# l-drv_h2.net
KiCad netlist of a schematic drawn in EAGLE
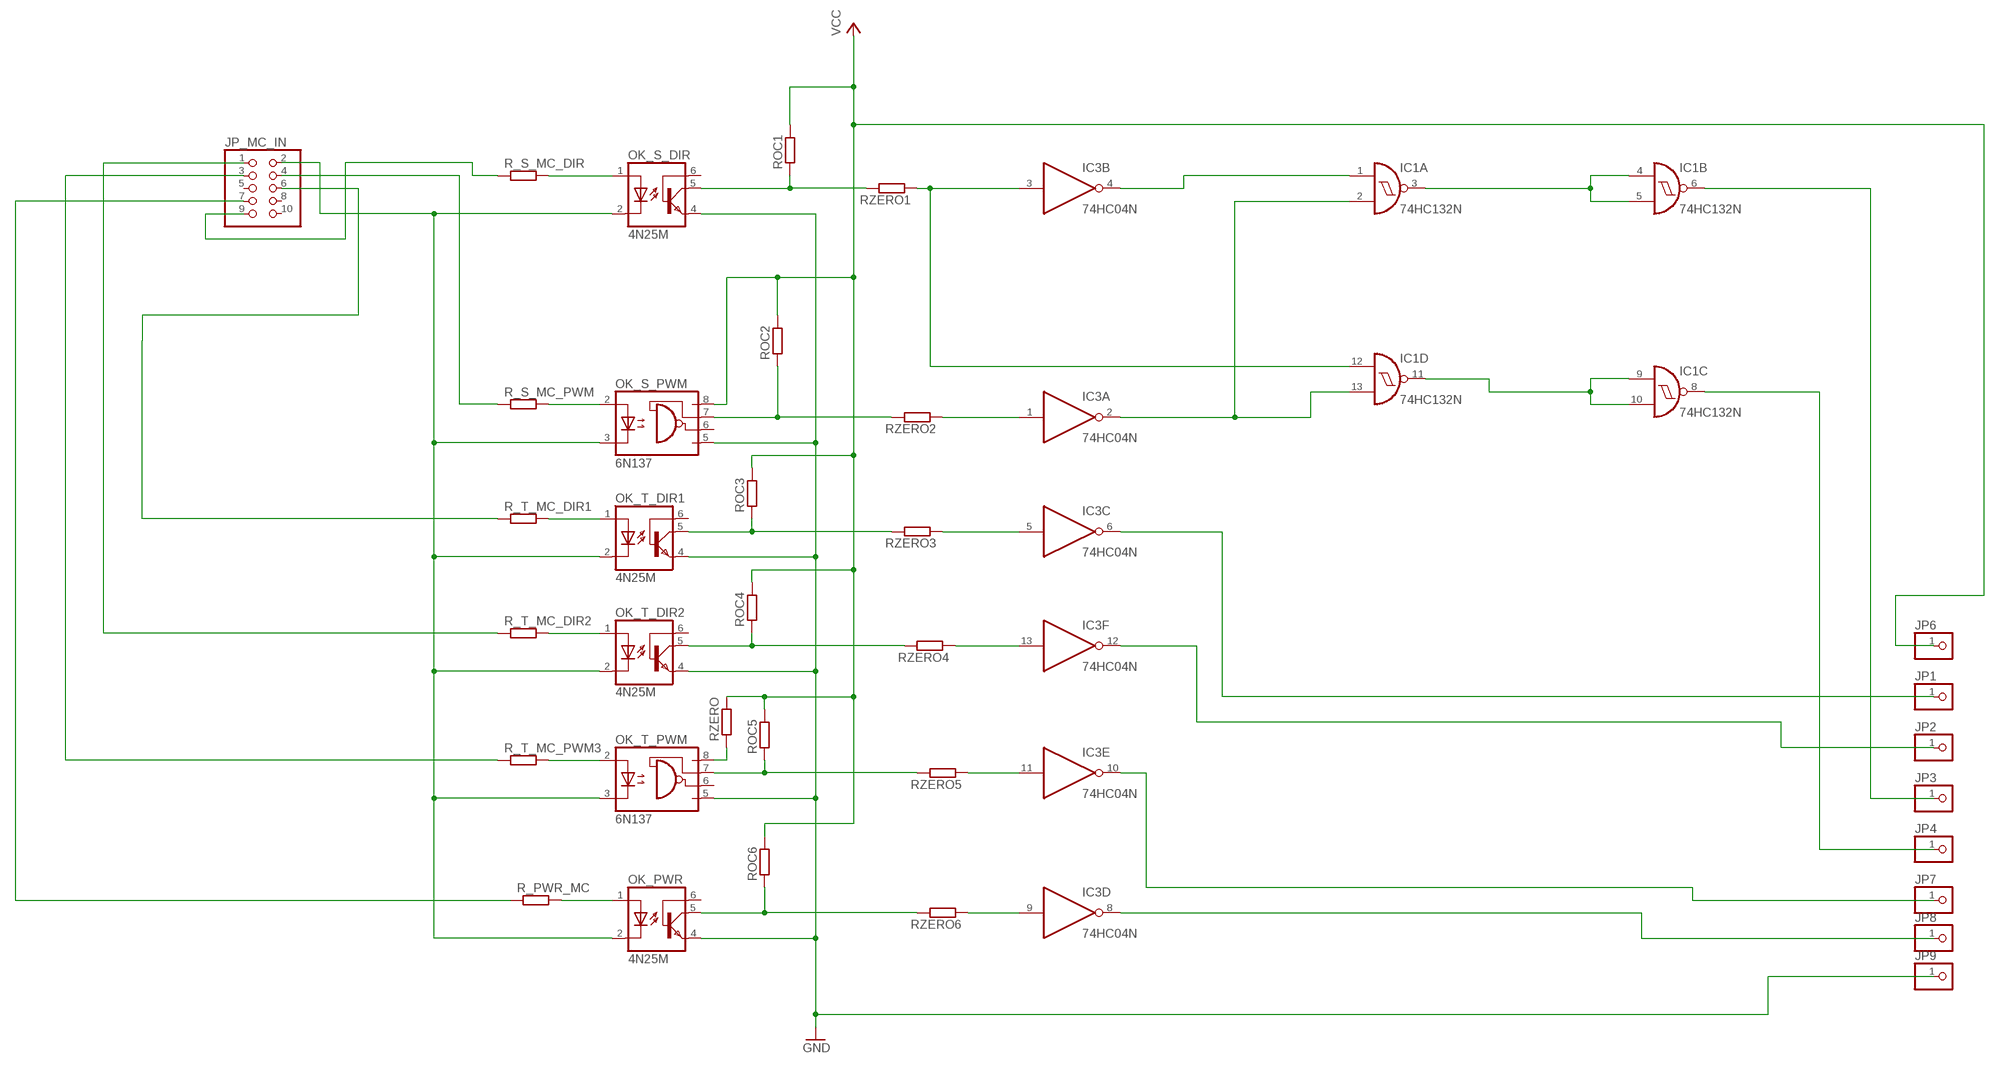
[diagram p0: schematic, sheet 1]

(export (version "E")
  (design (tool "Eeschema 10.0.6"))
  (components
    (comp (ref "IC1")
      (value "74HC132N")
      (footprint "eagle-import:DIL14")
      (libsource (lib "eagle-import") (part "74132NHC"))
    )
    (comp (ref "IC3")
      (value "74HC04N")
      (footprint "eagle-import:DIL14")
      (libsource (lib "eagle-import") (part "7404NHC"))
    )
    (comp (ref "JP1")
      (value "PINHD-1X1")
      (footprint "eagle-import:1X01")
      (libsource (lib "eagle-import") (part "PINHD-1X1"))
    )
    (comp (ref "JP2")
      (value "PINHD-1X1")
      (footprint "eagle-import:1X01")
      (libsource (lib "eagle-import") (part "PINHD-1X1"))
    )
    (comp (ref "JP3")
      (value "PINHD-1X1")
      (footprint "eagle-import:1X01")
      (libsource (lib "eagle-import") (part "PINHD-1X1"))
    )
    (comp (ref "JP4")
      (value "PINHD-1X1")
      (footprint "eagle-import:1X01")
      (libsource (lib "eagle-import") (part "PINHD-1X1"))
    )
    (comp (ref "JP6")
      (value "PINHD-1X1")
      (footprint "eagle-import:1X01")
      (libsource (lib "eagle-import") (part "PINHD-1X1"))
    )
    (comp (ref "JP7")
      (value "PINHD-1X1")
      (footprint "eagle-import:1X01")
      (libsource (lib "eagle-import") (part "PINHD-1X1"))
    )
    (comp (ref "JP8")
      (value "PINHD-1X1")
      (footprint "eagle-import:1X01")
      (libsource (lib "eagle-import") (part "PINHD-1X1"))
    )
    (comp (ref "JP9")
      (value "PINHD-1X1")
      (footprint "eagle-import:1X01")
      (libsource (lib "eagle-import") (part "PINHD-1X1"))
    )
    (comp (ref "JP_MC_IN")
      (value "PINHD-2X5")
      (footprint "eagle-import:2X05")
      (libsource (lib "eagle-import") (part "PINHD-2X5"))
    )
    (comp (ref "OK_PWR")
      (value "4N25M")
      (footprint "eagle-import:DIL06")
      (fields (field (name "MPN") "4N25-M"))
      (libsource (lib "eagle-import") (part "4N?M25"))
    )
    (comp (ref "OK_S_DIR")
      (value "4N25M")
      (footprint "eagle-import:DIL06")
      (fields (field (name "MPN") "4N25-M"))
      (libsource (lib "eagle-import") (part "4N?M25"))
    )
    (comp (ref "OK_S_PWM")
      (value "6N137")
      (footprint "eagle-import:DIL08")
      (libsource (lib "eagle-import") (part "6N137"))
    )
    (comp (ref "OK_T_DIR1")
      (value "4N25M")
      (footprint "eagle-import:DIL06")
      (fields (field (name "MPN") "4N25-M"))
      (libsource (lib "eagle-import") (part "4N?M25"))
    )
    (comp (ref "OK_T_DIR2")
      (value "4N25M")
      (footprint "eagle-import:DIL06")
      (fields (field (name "MPN") "4N25-M"))
      (libsource (lib "eagle-import") (part "4N?M25"))
    )
    (comp (ref "OK_T_PWM")
      (value "6N137")
      (footprint "eagle-import:DIL08")
      (libsource (lib "eagle-import") (part "6N137"))
    )
    (comp (ref "ROC1")
      (value "R-EU_0204/5")
      (footprint "eagle-import:0204_5")
      (libsource (lib "eagle-import") (part "R-EU_0204/5"))
    )
    (comp (ref "ROC2")
      (value "R-EU_0204/5")
      (footprint "eagle-import:0204_5")
      (libsource (lib "eagle-import") (part "R-EU_0204/5"))
    )
    (comp (ref "ROC3")
      (value "R-EU_0204/5")
      (footprint "eagle-import:0204_5")
      (libsource (lib "eagle-import") (part "R-EU_0204/5"))
    )
    (comp (ref "ROC4")
      (value "R-EU_0204/5")
      (footprint "eagle-import:0204_5")
      (libsource (lib "eagle-import") (part "R-EU_0204/5"))
    )
    (comp (ref "ROC5")
      (value "R-EU_0204/5")
      (footprint "eagle-import:0204_5")
      (libsource (lib "eagle-import") (part "R-EU_0204/5"))
    )
    (comp (ref "ROC6")
      (value "R-EU_0204/5")
      (footprint "eagle-import:0204_5")
      (libsource (lib "eagle-import") (part "R-EU_0204/5"))
    )
    (comp (ref "RZERO")
      (value "R-EU_0204/5")
      (footprint "eagle-import:0204_5")
      (libsource (lib "eagle-import") (part "R-EU_0204/5"))
    )
    (comp (ref "RZERO1")
      (value "R-EU_0204/5")
      (footprint "eagle-import:0204_5")
      (libsource (lib "eagle-import") (part "R-EU_0204/5"))
    )
    (comp (ref "RZERO2")
      (value "R-EU_0204/5")
      (footprint "eagle-import:0204_5")
      (libsource (lib "eagle-import") (part "R-EU_0204/5"))
    )
    (comp (ref "RZERO3")
      (value "R-EU_0204/5")
      (footprint "eagle-import:0204_5")
      (libsource (lib "eagle-import") (part "R-EU_0204/5"))
    )
    (comp (ref "RZERO4")
      (value "R-EU_0204/5")
      (footprint "eagle-import:0204_5")
      (libsource (lib "eagle-import") (part "R-EU_0204/5"))
    )
    (comp (ref "RZERO5")
      (value "R-EU_0204/5")
      (footprint "eagle-import:0204_5")
      (libsource (lib "eagle-import") (part "R-EU_0204/5"))
    )
    (comp (ref "RZERO6")
      (value "R-EU_0204/5")
      (footprint "eagle-import:0204_5")
      (libsource (lib "eagle-import") (part "R-EU_0204/5"))
    )
    (comp (ref "R_PWR_MC")
      (value "R-EU_0204/5")
      (footprint "eagle-import:0204_5")
      (libsource (lib "eagle-import") (part "R-EU_0204/5"))
    )
    (comp (ref "R_S_MC_DIR")
      (value "R-EU_0204/5")
      (footprint "eagle-import:0204_5")
      (libsource (lib "eagle-import") (part "R-EU_0204/5"))
    )
    (comp (ref "R_S_MC_PWM")
      (value "R-EU_0204/5")
      (footprint "eagle-import:0204_5")
      (libsource (lib "eagle-import") (part "R-EU_0204/5"))
    )
    (comp (ref "R_T_MC_DIR1")
      (value "R-EU_0204/5")
      (footprint "eagle-import:0204_5")
      (libsource (lib "eagle-import") (part "R-EU_0204/5"))
    )
    (comp (ref "R_T_MC_DIR2")
      (value "R-EU_0204/5")
      (footprint "eagle-import:0204_5")
      (libsource (lib "eagle-import") (part "R-EU_0204/5"))
    )
    (comp (ref "R_T_MC_PWM3")
      (value "R-EU_0204/5")
      (footprint "eagle-import:0204_5")
      (libsource (lib "eagle-import") (part "R-EU_0204/5"))
    )
  )
  (nets
    (net (code "1") (name "GND") (class "Default")
      (node (ref "JP9") (pin "1") (pinfunction "1_1") (pintype "passive"))
      (node (ref "OK_PWR") (pin "4") (pinfunction "EMI_4") (pintype "passive"))
      (node (ref "OK_S_DIR") (pin "4") (pinfunction "EMI_4") (pintype "passive"))
      (node (ref "OK_S_PWM") (pin "5") (pinfunction "GND_5") (pintype "passive"))
      (node (ref "OK_T_DIR1") (pin "4") (pinfunction "EMI_4") (pintype "passive"))
      (node (ref "OK_T_DIR2") (pin "4") (pinfunction "EMI_4") (pintype "passive"))
      (node (ref "OK_T_PWM") (pin "5") (pinfunction "GND_5") (pintype "passive"))
    )
    (net (code "2") (name "Net-(IC1A-I0)") (class "Default")
      (node (ref "IC1") (pin "1") (pinfunction "I0_1") (pintype "input"))
      (node (ref "IC3") (pin "4") (pinfunction "O_4") (pintype "output"))
    )
    (net (code "3") (name "Net-(IC1A-I1)") (class "Default")
      (node (ref "IC1") (pin "13") (pinfunction "I1_13") (pintype "input"))
      (node (ref "IC1") (pin "2") (pinfunction "I1_2") (pintype "input"))
      (node (ref "IC3") (pin "2") (pinfunction "O_2") (pintype "output"))
    )
    (net (code "4") (name "Net-(IC1A-O)") (class "Default")
      (node (ref "IC1") (pin "3") (pinfunction "O_3") (pintype "output"))
      (node (ref "IC1") (pin "4") (pinfunction "I0_4") (pintype "input"))
      (node (ref "IC1") (pin "5") (pinfunction "I1_5") (pintype "input"))
    )
    (net (code "5") (name "Net-(IC1B-O)") (class "Default")
      (node (ref "IC1") (pin "6") (pinfunction "O_6") (pintype "output"))
      (node (ref "JP3") (pin "1") (pinfunction "1_1") (pintype "passive"))
    )
    (net (code "6") (name "Net-(IC1C-I0)") (class "Default")
      (node (ref "IC1") (pin "10") (pinfunction "I1_10") (pintype "input"))
      (node (ref "IC1") (pin "11") (pinfunction "O_11") (pintype "output"))
      (node (ref "IC1") (pin "9") (pinfunction "I0_9") (pintype "input"))
    )
    (net (code "7") (name "Net-(IC1C-O)") (class "Default")
      (node (ref "IC1") (pin "8") (pinfunction "O_8") (pintype "output"))
      (node (ref "JP4") (pin "1") (pinfunction "1_1") (pintype "passive"))
    )
    (net (code "8") (name "Net-(IC1D-I0)") (class "Default")
      (node (ref "IC1") (pin "12") (pinfunction "I0_12") (pintype "input"))
      (node (ref "IC3") (pin "3") (pinfunction "I_3") (pintype "input"))
      (node (ref "RZERO1") (pin "1") (pinfunction "1_1") (pintype "passive"))
    )
    (net (code "9") (name "Net-(IC3A-I)") (class "Default")
      (node (ref "IC3") (pin "1") (pinfunction "I_1") (pintype "input"))
      (node (ref "RZERO2") (pin "1") (pinfunction "1_1") (pintype "passive"))
    )
    (net (code "10") (name "Net-(IC3C-I)") (class "Default")
      (node (ref "IC3") (pin "5") (pinfunction "I_5") (pintype "input"))
      (node (ref "RZERO3") (pin "1") (pinfunction "1_1") (pintype "passive"))
    )
    (net (code "11") (name "Net-(IC3C-O)") (class "Default")
      (node (ref "IC3") (pin "6") (pinfunction "O_6") (pintype "output"))
      (node (ref "JP1") (pin "1") (pinfunction "1_1") (pintype "passive"))
    )
    (net (code "12") (name "Net-(IC3D-I)") (class "Default")
      (node (ref "IC3") (pin "9") (pinfunction "I_9") (pintype "input"))
      (node (ref "RZERO6") (pin "1") (pinfunction "1_1") (pintype "passive"))
    )
    (net (code "13") (name "Net-(IC3D-O)") (class "Default")
      (node (ref "IC3") (pin "8") (pinfunction "O_8") (pintype "output"))
      (node (ref "JP8") (pin "1") (pinfunction "1_1") (pintype "passive"))
    )
    (net (code "14") (name "Net-(IC3E-I)") (class "Default")
      (node (ref "IC3") (pin "11") (pinfunction "I_11") (pintype "input"))
      (node (ref "RZERO5") (pin "1") (pinfunction "1_1") (pintype "passive"))
    )
    (net (code "15") (name "Net-(IC3E-O)") (class "Default")
      (node (ref "IC3") (pin "10") (pinfunction "O_10") (pintype "output"))
      (node (ref "JP7") (pin "1") (pinfunction "1_1") (pintype "passive"))
    )
    (net (code "16") (name "Net-(IC3F-I)") (class "Default")
      (node (ref "IC3") (pin "13") (pinfunction "I_13") (pintype "input"))
      (node (ref "RZERO4") (pin "1") (pinfunction "1_1") (pintype "passive"))
    )
    (net (code "17") (name "Net-(IC3F-O)") (class "Default")
      (node (ref "IC3") (pin "12") (pinfunction "O_12") (pintype "output"))
      (node (ref "JP2") (pin "1") (pinfunction "1_1") (pintype "passive"))
    )
    (net (code "18") (name "Net-(JP_MC_IN-Pad1)") (class "Default")
      (node (ref "JP_MC_IN") (pin "1") (pinfunction "1_1") (pintype "passive"))
      (node (ref "R_T_MC_DIR2") (pin "1") (pinfunction "1_1") (pintype "passive"))
    )
    (net (code "19") (name "Net-(JP_MC_IN-Pad3)") (class "Default")
      (node (ref "JP_MC_IN") (pin "3") (pinfunction "3_3") (pintype "passive"))
      (node (ref "R_T_MC_PWM3") (pin "1") (pinfunction "1_1") (pintype "passive"))
    )
    (net (code "20") (name "Net-(JP_MC_IN-Pad4)") (class "Default")
      (node (ref "JP_MC_IN") (pin "4") (pinfunction "4_4") (pintype "passive"))
      (node (ref "R_S_MC_PWM") (pin "1") (pinfunction "1_1") (pintype "passive"))
    )
    (net (code "21") (name "Net-(JP_MC_IN-Pad6)") (class "Default")
      (node (ref "JP_MC_IN") (pin "6") (pinfunction "6_6") (pintype "passive"))
      (node (ref "R_T_MC_DIR1") (pin "1") (pinfunction "1_1") (pintype "passive"))
    )
    (net (code "22") (name "Net-(JP_MC_IN-Pad7)") (class "Default")
      (node (ref "JP_MC_IN") (pin "7") (pinfunction "7_7") (pintype "passive"))
      (node (ref "R_PWR_MC") (pin "1") (pinfunction "1_1") (pintype "passive"))
    )
    (net (code "23") (name "Net-(JP_MC_IN-Pad9)") (class "Default")
      (node (ref "JP_MC_IN") (pin "9") (pinfunction "9_9") (pintype "passive"))
      (node (ref "R_S_MC_DIR") (pin "1") (pinfunction "1_1") (pintype "passive"))
    )
    (net (code "24") (name "Net-(OK_PWR-A)") (class "Default")
      (node (ref "OK_PWR") (pin "1") (pinfunction "A_1") (pintype "passive"))
      (node (ref "R_PWR_MC") (pin "2") (pinfunction "2_2") (pintype "passive"))
    )
    (net (code "25") (name "Net-(OK_PWR-C)") (class "Default")
      (node (ref "JP_MC_IN") (pin "2") (pinfunction "2_2") (pintype "passive"))
      (node (ref "OK_PWR") (pin "2") (pinfunction "C_2") (pintype "passive"))
      (node (ref "OK_S_DIR") (pin "2") (pinfunction "C_2") (pintype "passive"))
      (node (ref "OK_S_PWM") (pin "3") (pinfunction "C_3") (pintype "passive"))
      (node (ref "OK_T_DIR1") (pin "2") (pinfunction "C_2") (pintype "passive"))
      (node (ref "OK_T_DIR2") (pin "2") (pinfunction "C_2") (pintype "passive"))
      (node (ref "OK_T_PWM") (pin "3") (pinfunction "C_3") (pintype "passive"))
    )
    (net (code "26") (name "Net-(OK_PWR-COL)") (class "Default")
      (node (ref "OK_PWR") (pin "5") (pinfunction "COL_5") (pintype "passive"))
      (node (ref "ROC6") (pin "1") (pinfunction "1_1") (pintype "passive"))
      (node (ref "RZERO6") (pin "2") (pinfunction "2_2") (pintype "passive"))
    )
    (net (code "27") (name "Net-(OK_S_DIR-A)") (class "Default")
      (node (ref "OK_S_DIR") (pin "1") (pinfunction "A_1") (pintype "passive"))
      (node (ref "R_S_MC_DIR") (pin "2") (pinfunction "2_2") (pintype "passive"))
    )
    (net (code "28") (name "Net-(OK_S_DIR-COL)") (class "Default")
      (node (ref "OK_S_DIR") (pin "5") (pinfunction "COL_5") (pintype "passive"))
      (node (ref "ROC1") (pin "1") (pinfunction "1_1") (pintype "passive"))
      (node (ref "RZERO1") (pin "2") (pinfunction "2_2") (pintype "passive"))
    )
    (net (code "29") (name "Net-(OK_S_PWM-A)") (class "Default")
      (node (ref "OK_S_PWM") (pin "2") (pinfunction "A_2") (pintype "passive"))
      (node (ref "R_S_MC_PWM") (pin "2") (pinfunction "2_2") (pintype "passive"))
    )
    (net (code "30") (name "Net-(OK_S_PWM-VE)") (class "Default")
      (node (ref "OK_S_PWM") (pin "7") (pinfunction "VE_7") (pintype "passive"))
      (node (ref "ROC2") (pin "1") (pinfunction "1_1") (pintype "passive"))
      (node (ref "RZERO2") (pin "2") (pinfunction "2_2") (pintype "passive"))
    )
    (net (code "31") (name "Net-(OK_T_DIR1-A)") (class "Default")
      (node (ref "OK_T_DIR1") (pin "1") (pinfunction "A_1") (pintype "passive"))
      (node (ref "R_T_MC_DIR1") (pin "2") (pinfunction "2_2") (pintype "passive"))
    )
    (net (code "32") (name "Net-(OK_T_DIR1-COL)") (class "Default")
      (node (ref "OK_T_DIR1") (pin "5") (pinfunction "COL_5") (pintype "passive"))
      (node (ref "ROC3") (pin "1") (pinfunction "1_1") (pintype "passive"))
      (node (ref "RZERO3") (pin "2") (pinfunction "2_2") (pintype "passive"))
    )
    (net (code "33") (name "Net-(OK_T_DIR2-A)") (class "Default")
      (node (ref "OK_T_DIR2") (pin "1") (pinfunction "A_1") (pintype "passive"))
      (node (ref "R_T_MC_DIR2") (pin "2") (pinfunction "2_2") (pintype "passive"))
    )
    (net (code "34") (name "Net-(OK_T_DIR2-COL)") (class "Default")
      (node (ref "OK_T_DIR2") (pin "5") (pinfunction "COL_5") (pintype "passive"))
      (node (ref "ROC4") (pin "1") (pinfunction "1_1") (pintype "passive"))
      (node (ref "RZERO4") (pin "2") (pinfunction "2_2") (pintype "passive"))
    )
    (net (code "35") (name "Net-(OK_T_PWM-A)") (class "Default")
      (node (ref "OK_T_PWM") (pin "2") (pinfunction "A_2") (pintype "passive"))
      (node (ref "R_T_MC_PWM3") (pin "2") (pinfunction "2_2") (pintype "passive"))
    )
    (net (code "36") (name "Net-(OK_T_PWM-VCC)") (class "Default")
      (node (ref "OK_T_PWM") (pin "8") (pinfunction "VCC_8") (pintype "passive"))
      (node (ref "RZERO") (pin "1") (pinfunction "1_1") (pintype "passive"))
    )
    (net (code "37") (name "Net-(OK_T_PWM-VE)") (class "Default")
      (node (ref "OK_T_PWM") (pin "7") (pinfunction "VE_7") (pintype "passive"))
      (node (ref "ROC5") (pin "1") (pinfunction "1_1") (pintype "passive"))
      (node (ref "RZERO5") (pin "2") (pinfunction "2_2") (pintype "passive"))
    )
    (net (code "38") (name "VCC") (class "Default")
      (node (ref "JP6") (pin "1") (pinfunction "1_1") (pintype "passive"))
      (node (ref "OK_S_PWM") (pin "8") (pinfunction "VCC_8") (pintype "passive"))
      (node (ref "ROC1") (pin "2") (pinfunction "2_2") (pintype "passive"))
      (node (ref "ROC2") (pin "2") (pinfunction "2_2") (pintype "passive"))
      (node (ref "ROC3") (pin "2") (pinfunction "2_2") (pintype "passive"))
      (node (ref "ROC4") (pin "2") (pinfunction "2_2") (pintype "passive"))
      (node (ref "ROC5") (pin "2") (pinfunction "2_2") (pintype "passive"))
      (node (ref "ROC6") (pin "2") (pinfunction "2_2") (pintype "passive"))
      (node (ref "RZERO") (pin "2") (pinfunction "2_2") (pintype "passive"))
    )
    (net (code "39") (name "unconnected-(JP_MC_IN-Pad5)") (class "Default")
      (node (ref "JP_MC_IN") (pin "5") (pinfunction "5_5") (pintype "passive"))
    )
    (net (code "40") (name "unconnected-(JP_MC_IN-Pad8)") (class "Default")
      (node (ref "JP_MC_IN") (pin "8") (pinfunction "8_8") (pintype "passive"))
    )
    (net (code "41") (name "unconnected-(JP_MC_IN-Pad10)") (class "Default")
      (node (ref "JP_MC_IN") (pin "10") (pinfunction "10_10") (pintype "passive"))
    )
    (net (code "42") (name "unconnected-(OK_PWR-BAS-Pad6)") (class "Default")
      (node (ref "OK_PWR") (pin "6") (pinfunction "BAS_6") (pintype "passive"))
    )
    (net (code "43") (name "unconnected-(OK_S_DIR-BAS-Pad6)") (class "Default")
      (node (ref "OK_S_DIR") (pin "6") (pinfunction "BAS_6") (pintype "passive"))
    )
    (net (code "44") (name "unconnected-(OK_S_PWM-VO-Pad6)") (class "Default")
      (node (ref "OK_S_PWM") (pin "6") (pinfunction "VO_6") (pintype "passive"))
    )
    (net (code "45") (name "unconnected-(OK_T_DIR1-BAS-Pad6)") (class "Default")
      (node (ref "OK_T_DIR1") (pin "6") (pinfunction "BAS_6") (pintype "passive"))
    )
    (net (code "46") (name "unconnected-(OK_T_DIR2-BAS-Pad6)") (class "Default")
      (node (ref "OK_T_DIR2") (pin "6") (pinfunction "BAS_6") (pintype "passive"))
    )
    (net (code "47") (name "unconnected-(OK_T_PWM-VO-Pad6)") (class "Default")
      (node (ref "OK_T_PWM") (pin "6") (pinfunction "VO_6") (pintype "passive"))
    )
  )
)
